# Temp_NTC.net
KiCad netlist of a schematic drawn in Altium Designer
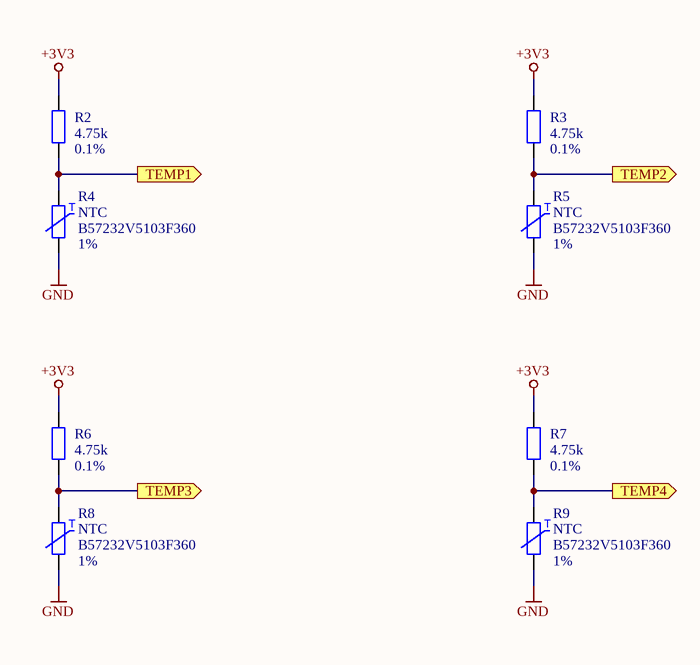
[diagram p0: Temp_NTC.SchDoc]

(export (version "E")
  (design (tool "Eeschema 10.0.6"))
  (components
    (comp (ref "R2")
      (value "4.75k")
      (footprint "R_0402")
      (fields
        (field (name "TOLERANCE") "0.1%")
        (field (name "PART NUMBER") "R_4.75k_50V_0402")
        (field (name "VOLTAGE") "50V")
        (field (name "MANUFACTURER") "Vishay")
      )
      (libsource (lib "ProgresjaSpace") (part "R"))
    )
    (comp (ref "R3")
      (value "4.75k")
      (footprint "R_0402")
      (fields
        (field (name "TOLERANCE") "0.1%")
        (field (name "PART NUMBER") "R_4.75k_50V_0402")
        (field (name "VOLTAGE") "50V")
        (field (name "MANUFACTURER") "Vishay")
      )
      (libsource (lib "ProgresjaSpace") (part "R"))
    )
    (comp (ref "R4")
      (value "B57232V5103F360")
      (footprint "R_0402")
      (description "NTC")
      (fields
        (field (name "DESC") "NTC")
        (field (name "TOLERANCE") "1%")
        (field (name "MANUFACTURER") "TDK")
        (field (name "Comment") "R_B572xxV5")
      )
      (libsource (lib "ProgresjaSpace") (part "R_B572xxV5"))
    )
    (comp (ref "R5")
      (value "B57232V5103F360")
      (footprint "R_0402")
      (description "NTC")
      (fields
        (field (name "DESC") "NTC")
        (field (name "TOLERANCE") "1%")
        (field (name "MANUFACTURER") "TDK")
        (field (name "Comment") "R_B572xxV5")
      )
      (libsource (lib "ProgresjaSpace") (part "R_B572xxV5"))
    )
    (comp (ref "R6")
      (value "4.75k")
      (footprint "R_0402")
      (fields
        (field (name "TOLERANCE") "0.1%")
        (field (name "PART NUMBER") "R_4.75k_50V_0402")
        (field (name "VOLTAGE") "50V")
        (field (name "MANUFACTURER") "Vishay")
      )
      (libsource (lib "ProgresjaSpace") (part "R"))
    )
    (comp (ref "R7")
      (value "4.75k")
      (footprint "R_0402")
      (fields
        (field (name "TOLERANCE") "0.1%")
        (field (name "PART NUMBER") "R_4.75k_50V_0402")
        (field (name "VOLTAGE") "50V")
        (field (name "MANUFACTURER") "Vishay")
      )
      (libsource (lib "ProgresjaSpace") (part "R"))
    )
    (comp (ref "R8")
      (value "B57232V5103F360")
      (footprint "R_0402")
      (description "NTC")
      (fields
        (field (name "DESC") "NTC")
        (field (name "TOLERANCE") "1%")
        (field (name "MANUFACTURER") "TDK")
        (field (name "Comment") "R_B572xxV5")
      )
      (libsource (lib "ProgresjaSpace") (part "R_B572xxV5"))
    )
    (comp (ref "R9")
      (value "B57232V5103F360")
      (footprint "R_0402")
      (description "NTC")
      (fields
        (field (name "DESC") "NTC")
        (field (name "TOLERANCE") "1%")
        (field (name "MANUFACTURER") "TDK")
        (field (name "Comment") "R_B572xxV5")
      )
      (libsource (lib "ProgresjaSpace") (part "R_B572xxV5"))
    )
  )
  (nets
    (net (code "1") (name "+3V3") (class "Default")
      (node (ref "R2") (pin "1") (pinfunction "1_1") (pintype "passive"))
      (node (ref "R3") (pin "1") (pinfunction "1_1") (pintype "passive"))
      (node (ref "R6") (pin "1") (pinfunction "1_1") (pintype "passive"))
      (node (ref "R7") (pin "1") (pinfunction "1_1") (pintype "passive"))
    )
    (net (code "2") (name "/TEMP1") (class "Default")
      (node (ref "R2") (pin "2") (pinfunction "2_2") (pintype "passive"))
      (node (ref "R4") (pin "1") (pinfunction "1_1") (pintype "passive"))
    )
    (net (code "3") (name "/TEMP2") (class "Default")
      (node (ref "R3") (pin "2") (pinfunction "2_2") (pintype "passive"))
      (node (ref "R5") (pin "1") (pinfunction "1_1") (pintype "passive"))
    )
    (net (code "4") (name "/TEMP3") (class "Default")
      (node (ref "R6") (pin "2") (pinfunction "2_2") (pintype "passive"))
      (node (ref "R8") (pin "1") (pinfunction "1_1") (pintype "passive"))
    )
    (net (code "5") (name "/TEMP4") (class "Default")
      (node (ref "R7") (pin "2") (pinfunction "2_2") (pintype "passive"))
      (node (ref "R9") (pin "1") (pinfunction "1_1") (pintype "passive"))
    )
    (net (code "6") (name "GND") (class "Default")
      (node (ref "R4") (pin "2") (pinfunction "2_2") (pintype "passive"))
      (node (ref "R5") (pin "2") (pinfunction "2_2") (pintype "passive"))
      (node (ref "R8") (pin "2") (pinfunction "2_2") (pintype "passive"))
      (node (ref "R9") (pin "2") (pinfunction "2_2") (pintype "passive"))
    )
  )
)
